# BBB-Supply.net
KiCad netlist of a schematic drawn in Altium Designer
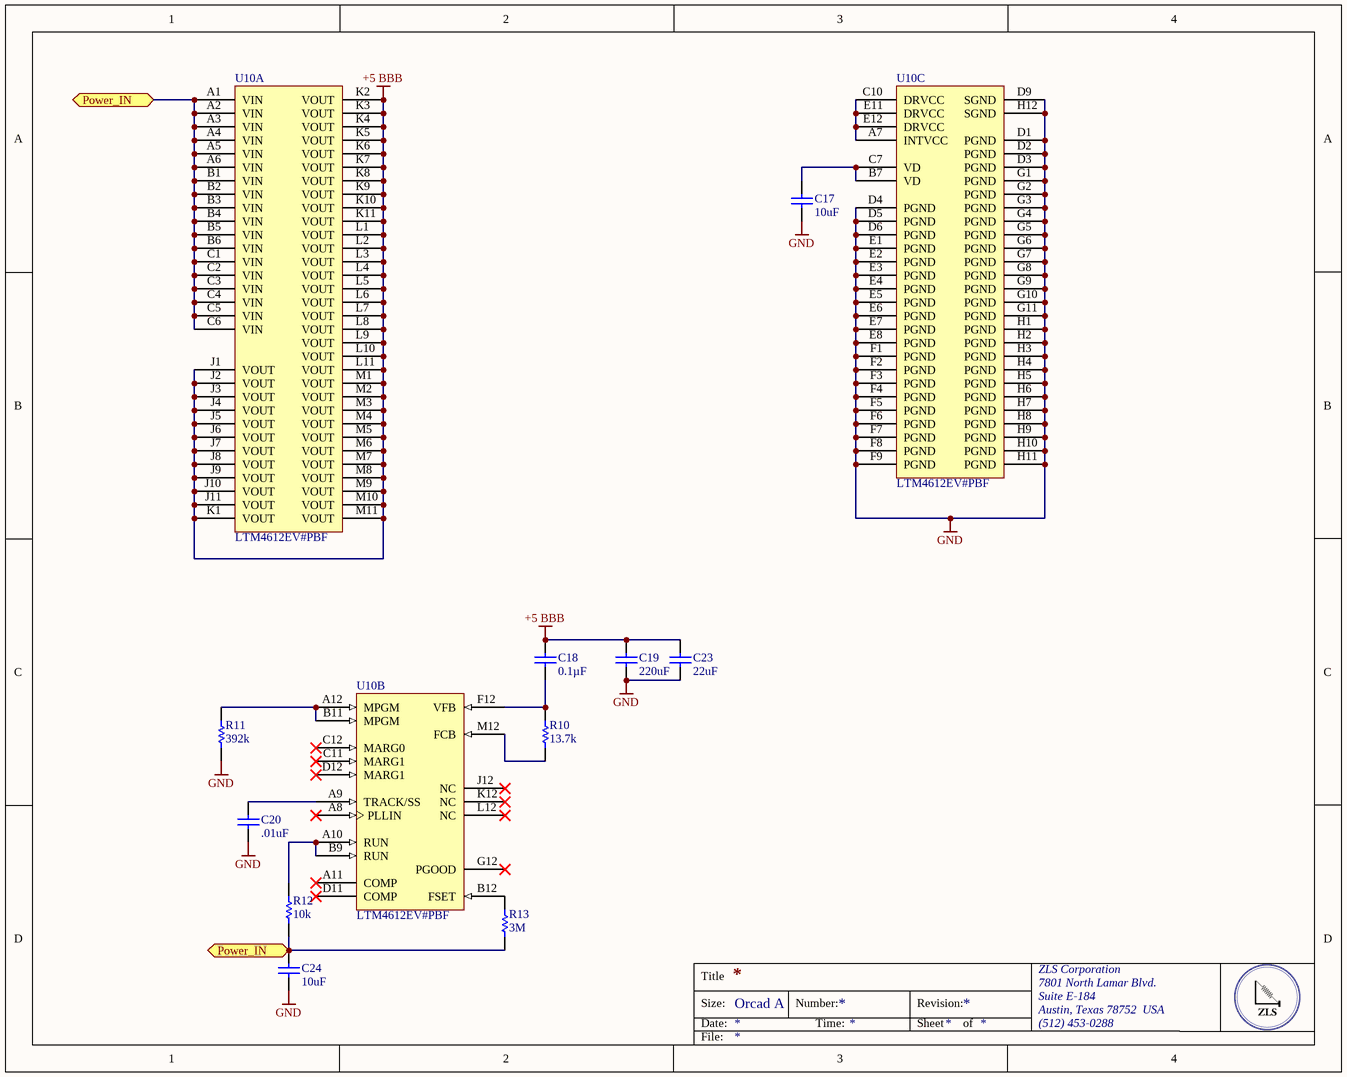
[diagram p0: BBB-Supply.SchDoc]

(export (version "E")
  (design (tool "Eeschema 10.0.6"))
  (components
    (comp (ref "C17")
      (value "CAP CER 0.1UF 16V X7R 0805")
      (footprint "CAPC0805(2012)145_N")
      (fields
        (field (name "TOLERANCE") "±10%")
        (field (name "MANUFACTURER") "Murata Electronics North America")
        (field (name "MANUFACTURER PART NUMBER") "GRM219R71C104KA01D")
        (field (name "CAPACITANCE") "10uF")
      )
      (libsource (lib "Altium Content Vault") (part "CMP-1036-04795-1"))
    )
    (comp (ref "C18")
      (value "CAP CER 0.1UF 16V X7R 0805")
      (footprint "CAPC0805(2012)145_N")
      (fields
        (field (name "TOLERANCE") "±10%")
        (field (name "MANUFACTURER") "Murata Electronics North America")
        (field (name "MANUFACTURER PART NUMBER") "GRM219R71C104KA01D")
        (field (name "CAPACITANCE") "0.1µF")
      )
      (libsource (lib "Altium Content Vault") (part "CMP-1036-04795-1"))
    )
    (comp (ref "C19")
      (value "CAP CER 0.1UF 16V X7R 0805")
      (footprint "CAPC0805(2012)145_N")
      (fields
        (field (name "TOLERANCE") "±10%")
        (field (name "MANUFACTURER") "Murata Electronics North America")
        (field (name "MANUFACTURER PART NUMBER") "GRM219R71C104KA01D")
        (field (name "CAPACITANCE") "220uF")
      )
      (libsource (lib "Altium Content Vault") (part "CMP-1036-04795-1"))
    )
    (comp (ref "C20")
      (value "CAP CER 0.1UF 16V X7R 0805")
      (footprint "CAPC0805(2012)145_N")
      (fields
        (field (name "TOLERANCE") "±10%")
        (field (name "MANUFACTURER") "Murata Electronics North America")
        (field (name "MANUFACTURER PART NUMBER") "GRM219R71C104KA01D")
        (field (name "CAPACITANCE") ".01uF")
      )
      (libsource (lib "Altium Content Vault") (part "CMP-1036-04795-1"))
    )
    (comp (ref "C23")
      (value "CAP CER 0.1UF 16V X7R 0805")
      (footprint "CAPC0805(2012)145_N")
      (fields
        (field (name "TOLERANCE") "±10%")
        (field (name "MANUFACTURER") "Murata Electronics North America")
        (field (name "MANUFACTURER PART NUMBER") "GRM219R71C104KA01D")
        (field (name "CAPACITANCE") "22uF")
      )
      (libsource (lib "Altium Content Vault") (part "CMP-1036-04795-1"))
    )
    (comp (ref "C24")
      (value "CAP CER 0.1UF 16V X7R 0805")
      (footprint "CAPC0805(2012)145_N")
      (fields
        (field (name "TOLERANCE") "±10%")
        (field (name "MANUFACTURER") "Murata Electronics North America")
        (field (name "MANUFACTURER PART NUMBER") "GRM219R71C104KA01D")
        (field (name "CAPACITANCE") "10uF")
      )
      (libsource (lib "Altium Content Vault") (part "CMP-1036-04795-1"))
    )
    (comp (ref "R10")
      (value "RES SMD 43K OHM 1% 1/8W 0805")
      (footprint "RESC0805(2012)_M")
      (description "RES SMD 10K OHM 1% 1/8W 0805")
      (fields (field (name "RESISTANCE (OHMS)") "13.7k"))
      (libsource (lib "Altium Content Vault") (part "CMP-1013-00017-1"))
    )
    (comp (ref "R11")
      (value "RES SMD 43K OHM 1% 1/8W 0805")
      (footprint "RESC0805(2012)_M")
      (description "RES SMD 10K OHM 1% 1/8W 0805")
      (fields (field (name "RESISTANCE (OHMS)") "392k"))
      (libsource (lib "Altium Content Vault") (part "CMP-1013-00017-1"))
    )
    (comp (ref "R12")
      (value "RES SMD 43K OHM 1% 1/8W 0805")
      (footprint "RESC0805(2012)_M")
      (description "RES SMD 10K OHM 1% 1/8W 0805")
      (fields (field (name "RESISTANCE (OHMS)") "10k"))
      (libsource (lib "Altium Content Vault") (part "CMP-1013-00017-1"))
    )
    (comp (ref "R13")
      (value "RES SMD 43K OHM 1% 1/8W 0805")
      (footprint "RESC0805(2012)_M")
      (description "RES SMD 10K OHM 1% 1/8W 0805")
      (fields (field (name "RESISTANCE (OHMS)") "3M"))
      (libsource (lib "Altium Content Vault") (part "CMP-1013-00017-1"))
    )
    (comp (ref "U10")
      (value "LTM4612EV#PBF")
      (footprint "LT-LGA-133-05-08-1766_V")
      (fields (field (name "MANUFACTURER") "Linear Technology"))
      (libsource (lib "Altium Content Vault") (part "LT-LTM4612-LGA-133"))
    )
  )
  (nets
    (net (code "1") (name "+5 BBB") (class "Default")
      (node (ref "C18") (pin "2") (pinfunction "2_2") (pintype "passive"))
      (node (ref "C19") (pin "2") (pinfunction "2_2") (pintype "passive"))
      (node (ref "C23") (pin "2") (pinfunction "2_2") (pintype "passive"))
      (node (ref "U10") (pin "J1") (pinfunction "VOUT_J1") (pintype "power_in"))
      (node (ref "U10") (pin "J10") (pinfunction "VOUT_J10") (pintype "power_in"))
      (node (ref "U10") (pin "J11") (pinfunction "VOUT_J11") (pintype "power_in"))
      (node (ref "U10") (pin "J2") (pinfunction "VOUT_J2") (pintype "power_in"))
      (node (ref "U10") (pin "J3") (pinfunction "VOUT_J3") (pintype "power_in"))
      (node (ref "U10") (pin "J4") (pinfunction "VOUT_J4") (pintype "power_in"))
      (node (ref "U10") (pin "J5") (pinfunction "VOUT_J5") (pintype "power_in"))
      (node (ref "U10") (pin "J6") (pinfunction "VOUT_J6") (pintype "power_in"))
      (node (ref "U10") (pin "J7") (pinfunction "VOUT_J7") (pintype "power_in"))
      (node (ref "U10") (pin "J8") (pinfunction "VOUT_J8") (pintype "power_in"))
      (node (ref "U10") (pin "J9") (pinfunction "VOUT_J9") (pintype "power_in"))
      (node (ref "U10") (pin "K1") (pinfunction "VOUT_K1") (pintype "power_in"))
      (node (ref "U10") (pin "K10") (pinfunction "VOUT_K10") (pintype "power_in"))
      (node (ref "U10") (pin "K11") (pinfunction "VOUT_K11") (pintype "power_in"))
      (node (ref "U10") (pin "K2") (pinfunction "VOUT_K2") (pintype "power_in"))
      (node (ref "U10") (pin "K3") (pinfunction "VOUT_K3") (pintype "power_in"))
      (node (ref "U10") (pin "K4") (pinfunction "VOUT_K4") (pintype "power_in"))
      (node (ref "U10") (pin "K5") (pinfunction "VOUT_K5") (pintype "power_in"))
      (node (ref "U10") (pin "K6") (pinfunction "VOUT_K6") (pintype "power_in"))
      (node (ref "U10") (pin "K7") (pinfunction "VOUT_K7") (pintype "power_in"))
      (node (ref "U10") (pin "K8") (pinfunction "VOUT_K8") (pintype "power_in"))
      (node (ref "U10") (pin "K9") (pinfunction "VOUT_K9") (pintype "power_in"))
      (node (ref "U10") (pin "L1") (pinfunction "VOUT_L1") (pintype "power_in"))
      (node (ref "U10") (pin "L10") (pinfunction "VOUT_L10") (pintype "power_in"))
      (node (ref "U10") (pin "L11") (pinfunction "VOUT_L11") (pintype "power_in"))
      (node (ref "U10") (pin "L2") (pinfunction "VOUT_L2") (pintype "power_in"))
      (node (ref "U10") (pin "L3") (pinfunction "VOUT_L3") (pintype "power_in"))
      (node (ref "U10") (pin "L4") (pinfunction "VOUT_L4") (pintype "power_in"))
      (node (ref "U10") (pin "L5") (pinfunction "VOUT_L5") (pintype "power_in"))
      (node (ref "U10") (pin "L6") (pinfunction "VOUT_L6") (pintype "power_in"))
      (node (ref "U10") (pin "L7") (pinfunction "VOUT_L7") (pintype "power_in"))
      (node (ref "U10") (pin "L8") (pinfunction "VOUT_L8") (pintype "power_in"))
      (node (ref "U10") (pin "L9") (pinfunction "VOUT_L9") (pintype "power_in"))
      (node (ref "U10") (pin "M1") (pinfunction "VOUT_M1") (pintype "power_in"))
      (node (ref "U10") (pin "M10") (pinfunction "VOUT_M10") (pintype "power_in"))
      (node (ref "U10") (pin "M11") (pinfunction "VOUT_M11") (pintype "power_in"))
      (node (ref "U10") (pin "M2") (pinfunction "VOUT_M2") (pintype "power_in"))
      (node (ref "U10") (pin "M3") (pinfunction "VOUT_M3") (pintype "power_in"))
      (node (ref "U10") (pin "M4") (pinfunction "VOUT_M4") (pintype "power_in"))
      (node (ref "U10") (pin "M5") (pinfunction "VOUT_M5") (pintype "power_in"))
      (node (ref "U10") (pin "M6") (pinfunction "VOUT_M6") (pintype "power_in"))
      (node (ref "U10") (pin "M7") (pinfunction "VOUT_M7") (pintype "power_in"))
      (node (ref "U10") (pin "M8") (pinfunction "VOUT_M8") (pintype "power_in"))
      (node (ref "U10") (pin "M9") (pinfunction "VOUT_M9") (pintype "power_in"))
    )
    (net (code "2") (name "/Power_IN") (class "Default")
      (node (ref "C24") (pin "2") (pinfunction "2_2") (pintype "passive"))
      (node (ref "R12") (pin "1") (pinfunction "1_1") (pintype "passive"))
      (node (ref "R13") (pin "1") (pinfunction "1_1") (pintype "passive"))
      (node (ref "U10") (pin "A1") (pinfunction "VIN_A1") (pintype "power_in"))
      (node (ref "U10") (pin "A2") (pinfunction "VIN_A2") (pintype "power_in"))
      (node (ref "U10") (pin "A3") (pinfunction "VIN_A3") (pintype "power_in"))
      (node (ref "U10") (pin "A4") (pinfunction "VIN_A4") (pintype "power_in"))
      (node (ref "U10") (pin "A5") (pinfunction "VIN_A5") (pintype "power_in"))
      (node (ref "U10") (pin "A6") (pinfunction "VIN_A6") (pintype "power_in"))
      (node (ref "U10") (pin "B1") (pinfunction "VIN_B1") (pintype "power_in"))
      (node (ref "U10") (pin "B2") (pinfunction "VIN_B2") (pintype "power_in"))
      (node (ref "U10") (pin "B3") (pinfunction "VIN_B3") (pintype "power_in"))
      (node (ref "U10") (pin "B4") (pinfunction "VIN_B4") (pintype "power_in"))
      (node (ref "U10") (pin "B5") (pinfunction "VIN_B5") (pintype "power_in"))
      (node (ref "U10") (pin "B6") (pinfunction "VIN_B6") (pintype "power_in"))
      (node (ref "U10") (pin "C1") (pinfunction "VIN_C1") (pintype "power_in"))
      (node (ref "U10") (pin "C2") (pinfunction "VIN_C2") (pintype "power_in"))
      (node (ref "U10") (pin "C3") (pinfunction "VIN_C3") (pintype "power_in"))
      (node (ref "U10") (pin "C4") (pinfunction "VIN_C4") (pintype "power_in"))
      (node (ref "U10") (pin "C5") (pinfunction "VIN_C5") (pintype "power_in"))
      (node (ref "U10") (pin "C6") (pinfunction "VIN_C6") (pintype "power_in"))
    )
    (net (code "3") (name "GND") (class "Default")
      (node (ref "C17") (pin "1") (pinfunction "1_1") (pintype "passive"))
      (node (ref "C19") (pin "1") (pinfunction "1_1") (pintype "passive"))
      (node (ref "C20") (pin "1") (pinfunction "1_1") (pintype "passive"))
      (node (ref "C23") (pin "1") (pinfunction "1_1") (pintype "passive"))
      (node (ref "C24") (pin "1") (pinfunction "1_1") (pintype "passive"))
      (node (ref "R11") (pin "1") (pinfunction "1_1") (pintype "passive"))
      (node (ref "U10") (pin "D1") (pinfunction "PGND_D1") (pintype "power_in"))
      (node (ref "U10") (pin "D2") (pinfunction "PGND_D2") (pintype "power_in"))
      (node (ref "U10") (pin "D3") (pinfunction "PGND_D3") (pintype "power_in"))
      (node (ref "U10") (pin "D4") (pinfunction "PGND_D4") (pintype "power_in"))
      (node (ref "U10") (pin "D5") (pinfunction "PGND_D5") (pintype "power_in"))
      (node (ref "U10") (pin "D6") (pinfunction "PGND_D6") (pintype "power_in"))
      (node (ref "U10") (pin "D9") (pinfunction "SGND_D9") (pintype "power_in"))
      (node (ref "U10") (pin "E1") (pinfunction "PGND_E1") (pintype "power_in"))
      (node (ref "U10") (pin "E2") (pinfunction "PGND_E2") (pintype "power_in"))
      (node (ref "U10") (pin "E3") (pinfunction "PGND_E3") (pintype "power_in"))
      (node (ref "U10") (pin "E4") (pinfunction "PGND_E4") (pintype "power_in"))
      (node (ref "U10") (pin "E5") (pinfunction "PGND_E5") (pintype "power_in"))
      (node (ref "U10") (pin "E6") (pinfunction "PGND_E6") (pintype "power_in"))
      (node (ref "U10") (pin "E7") (pinfunction "PGND_E7") (pintype "power_in"))
      (node (ref "U10") (pin "E8") (pinfunction "PGND_E8") (pintype "power_in"))
      (node (ref "U10") (pin "F1") (pinfunction "PGND_F1") (pintype "power_in"))
      (node (ref "U10") (pin "F2") (pinfunction "PGND_F2") (pintype "power_in"))
      (node (ref "U10") (pin "F3") (pinfunction "PGND_F3") (pintype "power_in"))
      (node (ref "U10") (pin "F4") (pinfunction "PGND_F4") (pintype "power_in"))
      (node (ref "U10") (pin "F5") (pinfunction "PGND_F5") (pintype "power_in"))
      (node (ref "U10") (pin "F6") (pinfunction "PGND_F6") (pintype "power_in"))
      (node (ref "U10") (pin "F7") (pinfunction "PGND_F7") (pintype "power_in"))
      (node (ref "U10") (pin "F8") (pinfunction "PGND_F8") (pintype "power_in"))
      (node (ref "U10") (pin "F9") (pinfunction "PGND_F9") (pintype "power_in"))
      (node (ref "U10") (pin "G1") (pinfunction "PGND_G1") (pintype "power_in"))
      (node (ref "U10") (pin "G10") (pinfunction "PGND_G10") (pintype "power_in"))
      (node (ref "U10") (pin "G11") (pinfunction "PGND_G11") (pintype "power_in"))
      (node (ref "U10") (pin "G2") (pinfunction "PGND_G2") (pintype "power_in"))
      (node (ref "U10") (pin "G3") (pinfunction "PGND_G3") (pintype "power_in"))
      (node (ref "U10") (pin "G4") (pinfunction "PGND_G4") (pintype "power_in"))
      (node (ref "U10") (pin "G5") (pinfunction "PGND_G5") (pintype "power_in"))
      (node (ref "U10") (pin "G6") (pinfunction "PGND_G6") (pintype "power_in"))
      (node (ref "U10") (pin "G7") (pinfunction "PGND_G7") (pintype "power_in"))
      (node (ref "U10") (pin "G8") (pinfunction "PGND_G8") (pintype "power_in"))
      (node (ref "U10") (pin "G9") (pinfunction "PGND_G9") (pintype "power_in"))
      (node (ref "U10") (pin "H1") (pinfunction "PGND_H1") (pintype "power_in"))
      (node (ref "U10") (pin "H10") (pinfunction "PGND_H10") (pintype "power_in"))
      (node (ref "U10") (pin "H11") (pinfunction "PGND_H11") (pintype "power_in"))
      (node (ref "U10") (pin "H12") (pinfunction "SGND_H12") (pintype "power_in"))
      (node (ref "U10") (pin "H2") (pinfunction "PGND_H2") (pintype "power_in"))
      (node (ref "U10") (pin "H3") (pinfunction "PGND_H3") (pintype "power_in"))
      (node (ref "U10") (pin "H4") (pinfunction "PGND_H4") (pintype "power_in"))
      (node (ref "U10") (pin "H5") (pinfunction "PGND_H5") (pintype "power_in"))
      (node (ref "U10") (pin "H6") (pinfunction "PGND_H6") (pintype "power_in"))
      (node (ref "U10") (pin "H7") (pinfunction "PGND_H7") (pintype "power_in"))
      (node (ref "U10") (pin "H8") (pinfunction "PGND_H8") (pintype "power_in"))
      (node (ref "U10") (pin "H9") (pinfunction "PGND_H9") (pintype "power_in"))
    )
    (net (code "4") (name "Net-(C17-Pad2)") (class "Default")
      (node (ref "C17") (pin "2") (pinfunction "2_2") (pintype "passive"))
      (node (ref "U10") (pin "B7") (pinfunction "VD_B7") (pintype "power_in"))
      (node (ref "U10") (pin "C7") (pinfunction "VD_C7") (pintype "power_in"))
    )
    (net (code "5") (name "Net-(R11-Pad2)") (class "Default")
      (node (ref "R11") (pin "2") (pinfunction "2_2") (pintype "passive"))
      (node (ref "U10") (pin "A12") (pinfunction "MPGM_A12") (pintype "input"))
      (node (ref "U10") (pin "B11") (pinfunction "MPGM_B11") (pintype "input"))
    )
    (net (code "6") (name "Net-(R12-Pad2)") (class "Default")
      (node (ref "R12") (pin "2") (pinfunction "2_2") (pintype "passive"))
      (node (ref "U10") (pin "A10") (pinfunction "RUN_A10") (pintype "input"))
      (node (ref "U10") (pin "B9") (pinfunction "RUN_B9") (pintype "input"))
    )
    (net (code "7") (name "Net-(U10B-FCB)") (class "Default")
      (node (ref "R10") (pin "2") (pinfunction "2_2") (pintype "passive"))
      (node (ref "U10") (pin "M12") (pinfunction "FCB_M12") (pintype "input"))
    )
    (net (code "8") (name "Net-(U10B-FSET)") (class "Default")
      (node (ref "R13") (pin "2") (pinfunction "2_2") (pintype "passive"))
      (node (ref "U10") (pin "B12") (pinfunction "FSET_B12") (pintype "input"))
    )
    (net (code "9") (name "Net-(U10B-TRACK{slash}SS)") (class "Default")
      (node (ref "C20") (pin "2") (pinfunction "2_2") (pintype "passive"))
      (node (ref "U10") (pin "A9") (pinfunction "TRACK/SS_A9") (pintype "input"))
    )
    (net (code "10") (name "Net-(U10B-VFB)") (class "Default")
      (node (ref "C18") (pin "1") (pinfunction "1_1") (pintype "passive"))
      (node (ref "R10") (pin "1") (pinfunction "1_1") (pintype "passive"))
      (node (ref "U10") (pin "F12") (pinfunction "VFB_F12") (pintype "input"))
    )
    (net (code "11") (name "Net-(U10C-INTVCC)") (class "Default")
      (node (ref "U10") (pin "A7") (pinfunction "INTVCC_A7") (pintype "power_in"))
      (node (ref "U10") (pin "C10") (pinfunction "DRVCC_C10") (pintype "power_in"))
      (node (ref "U10") (pin "E11") (pinfunction "DRVCC_E11") (pintype "power_in"))
      (node (ref "U10") (pin "E12") (pinfunction "DRVCC_E12") (pintype "power_in"))
    )
    (net (code "12") (name "unconnected-(U10B-COMP-PadA11)") (class "Default")
      (node (ref "U10") (pin "A11") (pinfunction "COMP_A11") (pintype "passive+no_connect"))
    )
    (net (code "13") (name "unconnected-(U10B-COMP-PadD11)") (class "Default")
      (node (ref "U10") (pin "D11") (pinfunction "COMP_D11") (pintype "passive+no_connect"))
    )
    (net (code "14") (name "unconnected-(U10B-MARG0-PadC12)") (class "Default")
      (node (ref "U10") (pin "C12") (pinfunction "MARG0_C12") (pintype "input+no_connect"))
    )
    (net (code "15") (name "unconnected-(U10B-MARG1-PadC11)") (class "Default")
      (node (ref "U10") (pin "C11") (pinfunction "MARG1_C11") (pintype "input+no_connect"))
    )
    (net (code "16") (name "unconnected-(U10B-MARG1-PadD12)") (class "Default")
      (node (ref "U10") (pin "D12") (pinfunction "MARG1_D12") (pintype "input+no_connect"))
    )
    (net (code "17") (name "unconnected-(U10B-NC-PadJ12)") (class "Default")
      (node (ref "U10") (pin "J12") (pinfunction "NC_J12") (pintype "passive+no_connect"))
    )
    (net (code "18") (name "unconnected-(U10B-NC-PadK12)") (class "Default")
      (node (ref "U10") (pin "K12") (pinfunction "NC_K12") (pintype "passive+no_connect"))
    )
    (net (code "19") (name "unconnected-(U10B-NC-PadL12)") (class "Default")
      (node (ref "U10") (pin "L12") (pinfunction "NC_L12") (pintype "passive+no_connect"))
    )
    (net (code "20") (name "unconnected-(U10B-PGOOD-PadG12)") (class "Default")
      (node (ref "U10") (pin "G12") (pinfunction "PGOOD_G12") (pintype "open_collector+no_connect"))
    )
    (net (code "21") (name "unconnected-(U10B-PLLIN-PadA8)") (class "Default")
      (node (ref "U10") (pin "A8") (pinfunction "PLLIN_A8") (pintype "input+no_connect"))
    )
  )
)
